# Adafruit_ESP8266_Feather_rev_E.net
KiCad netlist of a schematic drawn in EAGLE
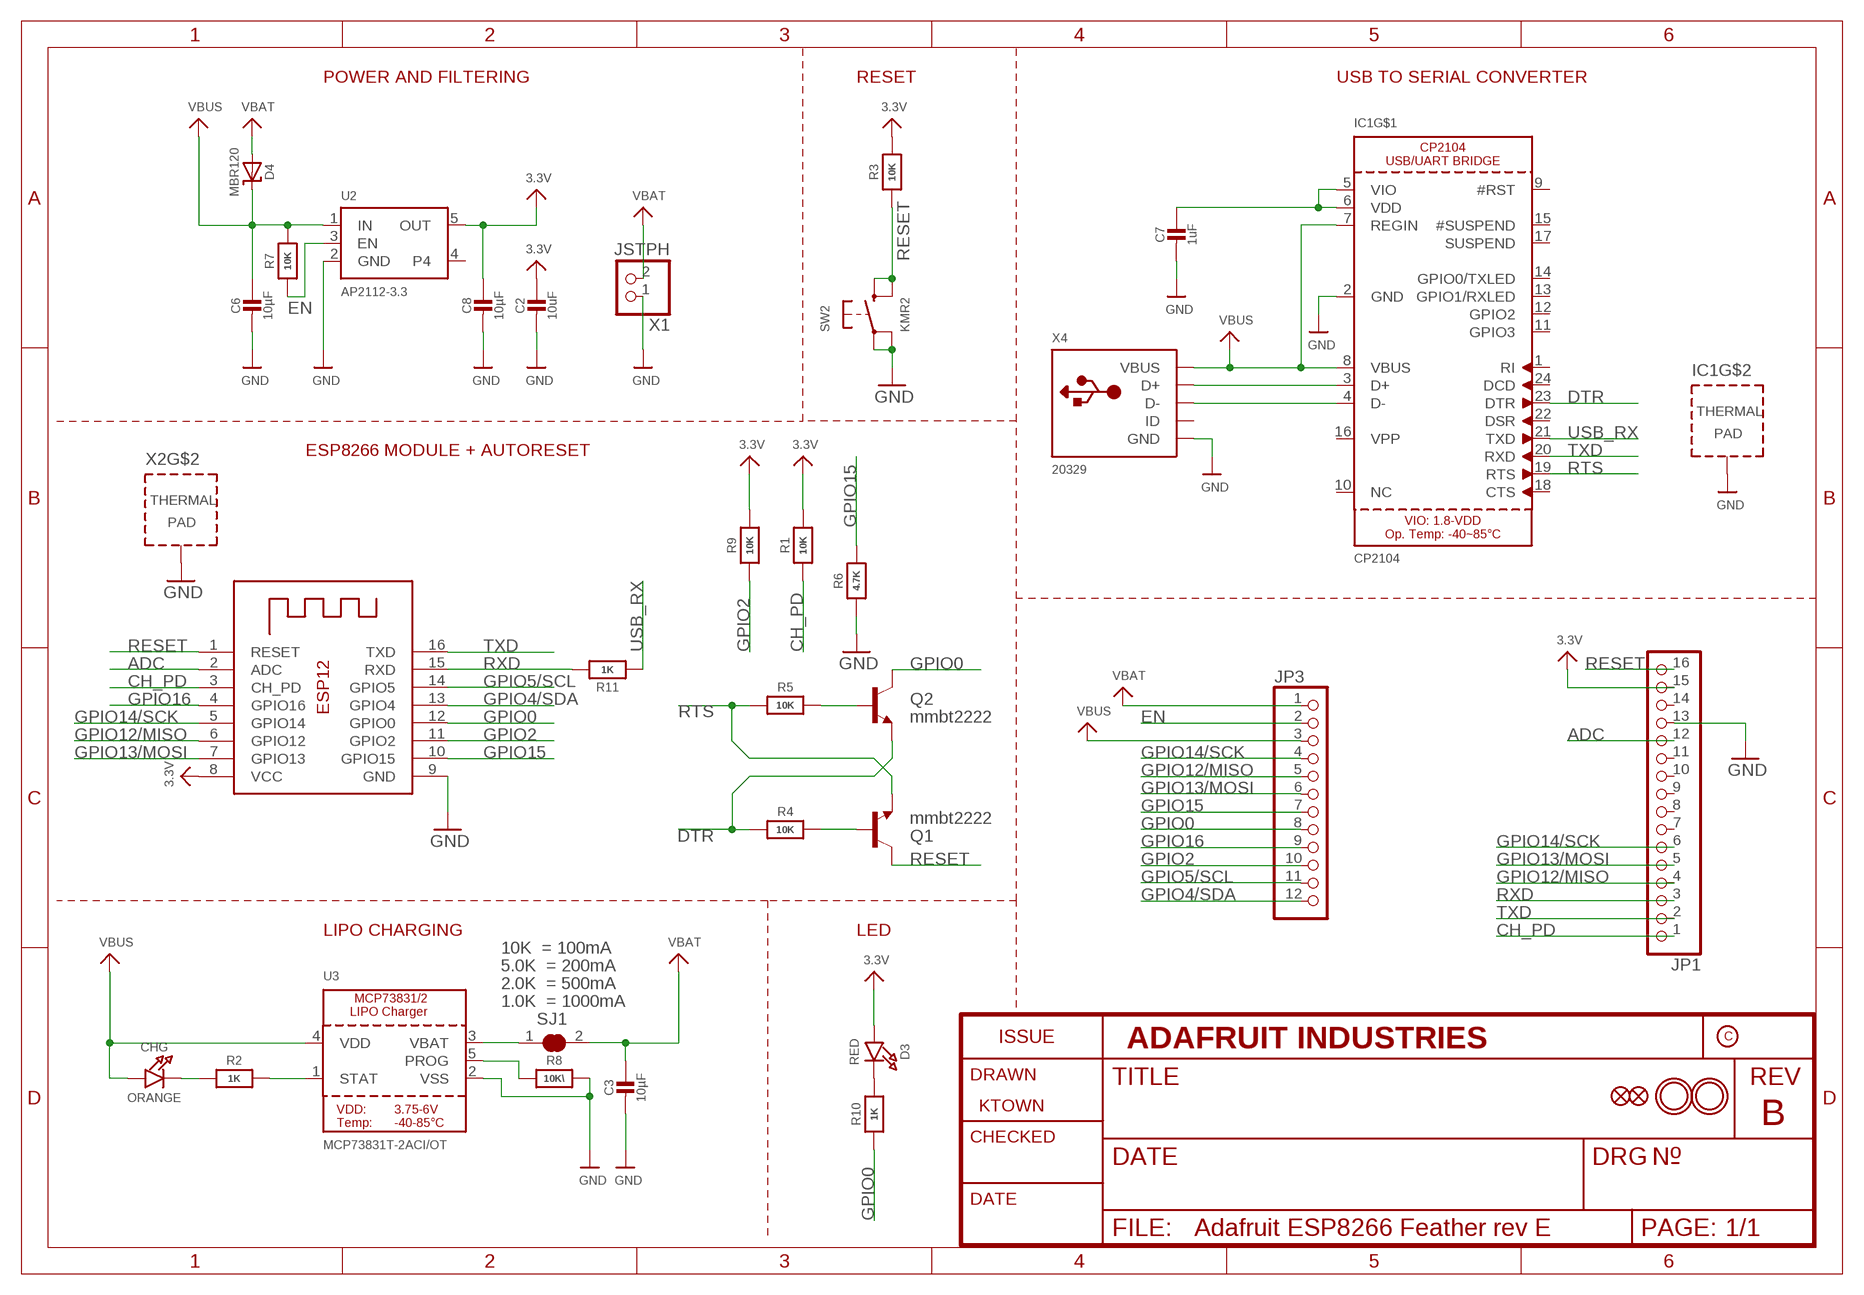
[diagram p0: schematic, sheet 1]

(export (version "E")
  (design (tool "Eeschema 10.0.6"))
  (components
    (comp (ref "C2")
      (value "10uF")
      (footprint "eagle-import:0805-NO")
      (libsource (lib "eagle-import") (part "CAP_CERAMIC0805-NOOUTLINE"))
    )
    (comp (ref "C3")
      (value "10µF")
      (footprint "eagle-import:0805-NO")
      (libsource (lib "eagle-import") (part "CAP_CERAMIC0805-NOOUTLINE"))
    )
    (comp (ref "C6")
      (value "10µF")
      (footprint "eagle-import:0805-NO")
      (libsource (lib "eagle-import") (part "CAP_CERAMIC0805-NOOUTLINE"))
    )
    (comp (ref "C7")
      (value "1uF")
      (footprint "eagle-import:0603-NO")
      (libsource (lib "eagle-import") (part "CAP_CERAMIC0603_NO"))
    )
    (comp (ref "C8")
      (value "10µF")
      (footprint "eagle-import:0805-NO")
      (libsource (lib "eagle-import") (part "CAP_CERAMIC0805-NOOUTLINE"))
    )
    (comp (ref "CHG")
      (value "ORANGE")
      (footprint "eagle-import:CHIPLED_0805_NOOUTLINE")
      (libsource (lib "eagle-import") (part "LED0805_NOOUTLINE"))
    )
    (comp (ref "D3")
      (value "RED")
      (footprint "eagle-import:CHIPLED_0805_NOOUTLINE")
      (libsource (lib "eagle-import") (part "LED0805_NOOUTLINE"))
    )
    (comp (ref "D4")
      (value "MBR120")
      (footprint "eagle-import:SOD-123")
      (libsource (lib "eagle-import") (part "DIODE-SCHOTTKYSOD-123"))
    )
    (comp (ref "IC1")
      (value "CP2104")
      (footprint "eagle-import:QFN24_4MM_SMSC")
      (libsource (lib "eagle-import") (part "CP2104"))
    )
    (comp (ref "JP1")
      (value "HEADER-1X16ROUND")
      (footprint "eagle-import:1X16_ROUND")
      (libsource (lib "eagle-import") (part "HEADER-1X16ROUND"))
    )
    (comp (ref "JP3")
      (value "HEADER-1X12")
      (footprint "eagle-import:1X12_ROUND")
      (libsource (lib "eagle-import") (part "HEADER-1X12"))
    )
    (comp (ref "Q1")
      (value "mmbt2222")
      (footprint "eagle-import:SOT23-3")
      (libsource (lib "eagle-import") (part "TRANSISTOR_NPNSOT23-3"))
    )
    (comp (ref "Q2")
      (value "mmbt2222")
      (footprint "eagle-import:SOT23-3")
      (libsource (lib "eagle-import") (part "TRANSISTOR_NPNSOT23-3"))
    )
    (comp (ref "R1")
      (value "10K")
      (footprint "eagle-import:0603-NO")
      (libsource (lib "eagle-import") (part "RESISTOR_0603_NOOUT"))
    )
    (comp (ref "R2")
      (value "1K")
      (footprint "eagle-import:0603-NO")
      (libsource (lib "eagle-import") (part "RESISTOR_0603_NOOUT"))
    )
    (comp (ref "R3")
      (value "10K")
      (footprint "eagle-import:0603-NO")
      (libsource (lib "eagle-import") (part "RESISTOR_0603_NOOUT"))
    )
    (comp (ref "R4")
      (value "10K")
      (footprint "eagle-import:0603-NO")
      (libsource (lib "eagle-import") (part "RESISTOR_0603_NOOUT"))
    )
    (comp (ref "R5")
      (value "10K")
      (footprint "eagle-import:0603-NO")
      (libsource (lib "eagle-import") (part "RESISTOR_0603_NOOUT"))
    )
    (comp (ref "R6")
      (value "4.7K")
      (footprint "eagle-import:0603-NO")
      (libsource (lib "eagle-import") (part "RESISTOR_0603_NOOUT"))
    )
    (comp (ref "R7")
      (value "10K")
      (footprint "eagle-import:0603-NO")
      (libsource (lib "eagle-import") (part "RESISTOR_0603_NOOUT"))
    )
    (comp (ref "R8")
      (value "10K\\")
      (footprint "eagle-import:0603-NO")
      (libsource (lib "eagle-import") (part "RESISTOR_0603_NOOUT"))
    )
    (comp (ref "R9")
      (value "10K")
      (footprint "eagle-import:0603-NO")
      (libsource (lib "eagle-import") (part "RESISTOR_0603_NOOUT"))
    )
    (comp (ref "R10")
      (value "1K")
      (footprint "eagle-import:0603-NO")
      (libsource (lib "eagle-import") (part "RESISTOR_0603_NOOUT"))
    )
    (comp (ref "R11")
      (value "1K")
      (footprint "eagle-import:_0603MP")
      (libsource (lib "eagle-import") (part "RESISTOR_0603MP"))
    )
    (comp (ref "SJ1")
      (value "SOLDERJUMPER_CLOSED")
      (footprint "eagle-import:SOLDERJUMPER_CLOSEDWIRE")
      (libsource (lib "eagle-import") (part "SOLDERJUMPER_CLOSED"))
    )
    (comp (ref "SW2")
      (value "KMR2")
      (footprint "eagle-import:BTN_KMR2_4.6X2.8")
      (libsource (lib "eagle-import") (part "SWITCH_TACT_SMT4.6X2.8"))
    )
    (comp (ref "U$31")
      (value "MOUNTINGHOLE2.5")
      (footprint "eagle-import:MOUNTINGHOLE_2.5_PLATED")
      (libsource (lib "eagle-import") (part "MOUNTINGHOLE2.5"))
    )
    (comp (ref "U$32")
      (value "MOUNTINGHOLE2.5")
      (footprint "eagle-import:MOUNTINGHOLE_2.5_PLATED")
      (libsource (lib "eagle-import") (part "MOUNTINGHOLE2.5"))
    )
    (comp (ref "U$34")
      (value "FIDUCIAL_1MM")
      (footprint "eagle-import:FIDUCIAL_1MM")
      (libsource (lib "eagle-import") (part "FIDUCIAL_1MM"))
    )
    (comp (ref "U$35")
      (value "FIDUCIAL_1MM")
      (footprint "eagle-import:FIDUCIAL_1MM")
      (libsource (lib "eagle-import") (part "FIDUCIAL_1MM"))
    )
    (comp (ref "U2")
      (value "AP2112-3.3")
      (footprint "eagle-import:SOT23-5")
      (libsource (lib "eagle-import") (part "VREG_SOT23-5"))
    )
    (comp (ref "U3")
      (value "MCP73831T-2ACI/OT")
      (footprint "eagle-import:SOT23-5")
      (libsource (lib "eagle-import") (part "MCP73831/2"))
    )
    (comp (ref "X1")
      (value "JSTPH")
      (footprint "eagle-import:JSTPH2")
      (libsource (lib "eagle-import") (part "CON_JST_PH_2PIN"))
    )
    (comp (ref "X2")
      (value "ESP-12")
      (footprint "eagle-import:ESP-12S")
      (libsource (lib "eagle-import") (part "ESP-12S"))
    )
    (comp (ref "X4")
      (value "20329")
      (footprint "eagle-import:4UCONN_20329_V2")
      (libsource (lib "eagle-import") (part "USB_MICRO_20329_V2"))
    )
  )
  (nets
    (net (code "1") (name "/ADC") (class "Default")
      (node (ref "JP1") (pin "12") (pinfunction "12_12") (pintype "passive"))
      (node (ref "X2") (pin "2") (pinfunction "ADC_2") (pintype "passive"))
    )
    (net (code "2") (name "/CH_PD") (class "Default")
      (node (ref "JP1") (pin "1") (pinfunction "1_1") (pintype "passive"))
      (node (ref "R1") (pin "1") (pinfunction "1_1") (pintype "passive"))
      (node (ref "X2") (pin "3") (pinfunction "CH_PD_3") (pintype "input"))
    )
    (net (code "3") (name "/DTR") (class "Default")
      (node (ref "IC1") (pin "23") (pinfunction "DTR_23") (pintype "output"))
      (node (ref "Q2") (pin "2") (pinfunction "E_2") (pintype "passive"))
      (node (ref "R4") (pin "1") (pinfunction "1_1") (pintype "passive"))
    )
    (net (code "4") (name "/EN") (class "Default")
      (node (ref "JP3") (pin "2") (pinfunction "2_2") (pintype "passive"))
      (node (ref "R7") (pin "1") (pinfunction "1_1") (pintype "passive"))
      (node (ref "U2") (pin "3") (pinfunction "EN_3") (pintype "input"))
    )
    (net (code "5") (name "/GPIO0") (class "Default")
      (node (ref "JP3") (pin "8") (pinfunction "8_8") (pintype "passive"))
      (node (ref "Q2") (pin "3") (pinfunction "C_3") (pintype "passive"))
      (node (ref "R10") (pin "1") (pinfunction "1_1") (pintype "passive"))
      (node (ref "X2") (pin "12") (pinfunction "GPIO0_12") (pintype "bidirectional"))
    )
    (net (code "6") (name "/GPIO2") (class "Default")
      (node (ref "JP3") (pin "10") (pinfunction "10_10") (pintype "passive"))
      (node (ref "R9") (pin "1") (pinfunction "1_1") (pintype "passive"))
      (node (ref "X2") (pin "11") (pinfunction "GPIO2_11") (pintype "bidirectional"))
    )
    (net (code "7") (name "/GPIO4{slash}SDA") (class "Default")
      (node (ref "JP3") (pin "12") (pinfunction "12_12") (pintype "passive"))
      (node (ref "X2") (pin "13") (pinfunction "GPIO4_13") (pintype "bidirectional"))
    )
    (net (code "8") (name "/GPIO5{slash}SCL") (class "Default")
      (node (ref "JP3") (pin "11") (pinfunction "11_11") (pintype "passive"))
      (node (ref "X2") (pin "14") (pinfunction "GPIO5_14") (pintype "bidirectional"))
    )
    (net (code "9") (name "/GPIO12{slash}MISO") (class "Default")
      (node (ref "JP1") (pin "4") (pinfunction "4_4") (pintype "passive"))
      (node (ref "JP3") (pin "5") (pinfunction "5_5") (pintype "passive"))
      (node (ref "X2") (pin "6") (pinfunction "GPIO12_6") (pintype "bidirectional"))
    )
    (net (code "10") (name "/GPIO13{slash}MOSI") (class "Default")
      (node (ref "JP1") (pin "5") (pinfunction "5_5") (pintype "passive"))
      (node (ref "JP3") (pin "6") (pinfunction "6_6") (pintype "passive"))
      (node (ref "X2") (pin "7") (pinfunction "GPIO13_7") (pintype "bidirectional"))
    )
    (net (code "11") (name "/GPIO14{slash}SCK") (class "Default")
      (node (ref "JP1") (pin "6") (pinfunction "6_6") (pintype "passive"))
      (node (ref "JP3") (pin "4") (pinfunction "4_4") (pintype "passive"))
      (node (ref "X2") (pin "5") (pinfunction "GPIO14_5") (pintype "bidirectional"))
    )
    (net (code "12") (name "/GPIO15") (class "Default")
      (node (ref "JP3") (pin "7") (pinfunction "7_7") (pintype "passive"))
      (node (ref "R6") (pin "2") (pinfunction "2_2") (pintype "passive"))
      (node (ref "X2") (pin "10") (pinfunction "GPIO15_10") (pintype "bidirectional"))
    )
    (net (code "13") (name "/GPIO16") (class "Default")
      (node (ref "JP3") (pin "9") (pinfunction "9_9") (pintype "passive"))
      (node (ref "X2") (pin "4") (pinfunction "GPIO16_4") (pintype "bidirectional"))
    )
    (net (code "14") (name "/RESET") (class "Default")
      (node (ref "JP1") (pin "16") (pinfunction "16_16") (pintype "passive"))
      (node (ref "Q1") (pin "3") (pinfunction "C_3") (pintype "passive"))
      (node (ref "R3") (pin "1") (pinfunction "1_1") (pintype "passive"))
      (node (ref "SW2") (pin "B") (pinfunction "S_B") (pintype "passive"))
      (node (ref "SW2") (pin "B'") (pinfunction "S1_B'") (pintype "passive"))
      (node (ref "X2") (pin "1") (pinfunction "RESET_1") (pintype "input"))
    )
    (net (code "15") (name "/RTS") (class "Default")
      (node (ref "IC1") (pin "19") (pinfunction "RTS_19") (pintype "output"))
      (node (ref "Q1") (pin "2") (pinfunction "E_2") (pintype "passive"))
      (node (ref "R5") (pin "1") (pinfunction "1_1") (pintype "passive"))
    )
    (net (code "16") (name "/RXD") (class "Default")
      (node (ref "JP1") (pin "3") (pinfunction "3_3") (pintype "passive"))
      (node (ref "R11") (pin "2") (pinfunction "2_2") (pintype "passive"))
      (node (ref "X2") (pin "15") (pinfunction "RXD_15") (pintype "input"))
    )
    (net (code "17") (name "/TXD") (class "Default")
      (node (ref "IC1") (pin "20") (pinfunction "RXD_20") (pintype "input"))
      (node (ref "JP1") (pin "2") (pinfunction "2_2") (pintype "passive"))
      (node (ref "X2") (pin "16") (pinfunction "TXD_16") (pintype "output"))
    )
    (net (code "18") (name "/USB_RX") (class "Default")
      (node (ref "IC1") (pin "21") (pinfunction "TXD_21") (pintype "output"))
      (node (ref "R11") (pin "1") (pinfunction "1_1") (pintype "passive"))
    )
    (net (code "19") (name "3.3V") (class "Default")
      (node (ref "C2") (pin "1") (pinfunction "1_1") (pintype "passive"))
      (node (ref "C8") (pin "1") (pinfunction "1_1") (pintype "passive"))
      (node (ref "D3") (pin "A") (pinfunction "A_A") (pintype "passive"))
      (node (ref "JP1") (pin "15") (pinfunction "15_15") (pintype "passive"))
      (node (ref "R1") (pin "2") (pinfunction "2_2") (pintype "passive"))
      (node (ref "R3") (pin "2") (pinfunction "2_2") (pintype "passive"))
      (node (ref "R9") (pin "2") (pinfunction "2_2") (pintype "passive"))
      (node (ref "U2") (pin "5") (pinfunction "OUT_5") (pintype "power_in"))
      (node (ref "X2") (pin "8") (pinfunction "VCC_8") (pintype "power_in"))
    )
    (net (code "20") (name "GND") (class "Default")
      (node (ref "C2") (pin "2") (pinfunction "2_2") (pintype "passive"))
      (node (ref "C3") (pin "2") (pinfunction "2_2") (pintype "passive"))
      (node (ref "C6") (pin "2") (pinfunction "2_2") (pintype "passive"))
      (node (ref "C7") (pin "2") (pinfunction "2_2") (pintype "passive"))
      (node (ref "C8") (pin "2") (pinfunction "2_2") (pintype "passive"))
      (node (ref "IC1") (pin "2") (pinfunction "GND_2") (pintype "power_in"))
      (node (ref "IC1") (pin "THERM") (pinfunction "TP_THERM") (pintype "power_in"))
      (node (ref "JP1") (pin "13") (pinfunction "13_13") (pintype "passive"))
      (node (ref "R6") (pin "1") (pinfunction "1_1") (pintype "passive"))
      (node (ref "R8") (pin "2") (pinfunction "2_2") (pintype "passive"))
      (node (ref "SW2") (pin "A") (pinfunction "P_A") (pintype "passive"))
      (node (ref "SW2") (pin "A'") (pinfunction "P1_A'") (pintype "passive"))
      (node (ref "U2") (pin "2") (pinfunction "GND_2") (pintype "power_in"))
      (node (ref "U3") (pin "2") (pinfunction "VSS_2") (pintype "power_in"))
      (node (ref "X1") (pin "1") (pinfunction "1_1") (pintype "passive"))
      (node (ref "X2") (pin "9") (pinfunction "GND_9") (pintype "power_in"))
      (node (ref "X2") (pin "P$1") (pinfunction "TP_P$1") (pintype "power_in"))
      (node (ref "X4") (pin "BASE@1") (pinfunction "GND_BASE@1") (pintype "power_in"))
      (node (ref "X4") (pin "BASE@2") (pinfunction "GND_BASE@2") (pintype "power_in"))
      (node (ref "X4") (pin "GND") (pinfunction "GND_GND") (pintype "power_in"))
      (node (ref "X4") (pin "SPRT@1") (pinfunction "GND_SPRT@1") (pintype "power_in"))
      (node (ref "X4") (pin "SPRT@2") (pinfunction "GND_SPRT@2") (pintype "power_in"))
      (node (ref "X4") (pin "SPRT@3") (pinfunction "GND_SPRT@3") (pintype "power_in"))
      (node (ref "X4") (pin "SPRT@4") (pinfunction "GND_SPRT@4") (pintype "power_in"))
    )
    (net (code "21") (name "Net-(CHG-PadC)") (class "Default")
      (node (ref "CHG") (pin "C") (pinfunction "C_C") (pintype "passive"))
      (node (ref "R2") (pin "1") (pinfunction "1_1") (pintype "passive"))
    )
    (net (code "22") (name "Net-(D3-PadC)") (class "Default")
      (node (ref "D3") (pin "C") (pinfunction "C_C") (pintype "passive"))
      (node (ref "R10") (pin "2") (pinfunction "2_2") (pintype "passive"))
    )
    (net (code "23") (name "Net-(IC1A-D+)") (class "Default")
      (node (ref "IC1") (pin "3") (pinfunction "D+_3") (pintype "bidirectional"))
      (node (ref "X4") (pin "D+") (pinfunction "D+_D+") (pintype "bidirectional"))
    )
    (net (code "24") (name "Net-(IC1A-D-)") (class "Default")
      (node (ref "IC1") (pin "4") (pinfunction "D-_4") (pintype "bidirectional"))
      (node (ref "X4") (pin "D-") (pinfunction "D-_D-") (pintype "bidirectional"))
    )
    (net (code "25") (name "Net-(IC1A-VDD)") (class "Default")
      (node (ref "C7") (pin "1") (pinfunction "1_1") (pintype "passive"))
      (node (ref "IC1") (pin "5") (pinfunction "VIO_5") (pintype "power_in"))
      (node (ref "IC1") (pin "6") (pinfunction "VDD_6") (pintype "power_in"))
    )
    (net (code "26") (name "Net-(Q1-B)") (class "Default")
      (node (ref "Q1") (pin "1") (pinfunction "B_1") (pintype "passive"))
      (node (ref "R4") (pin "2") (pinfunction "2_2") (pintype "passive"))
    )
    (net (code "27") (name "Net-(Q2-B)") (class "Default")
      (node (ref "Q2") (pin "1") (pinfunction "B_1") (pintype "passive"))
      (node (ref "R5") (pin "2") (pinfunction "2_2") (pintype "passive"))
    )
    (net (code "28") (name "Net-(U3-PROG)") (class "Default")
      (node (ref "R8") (pin "1") (pinfunction "1_1") (pintype "passive"))
      (node (ref "U3") (pin "5") (pinfunction "PROG_5") (pintype "input"))
    )
    (net (code "29") (name "Net-(U3-STAT)") (class "Default")
      (node (ref "R2") (pin "2") (pinfunction "2_2") (pintype "passive"))
      (node (ref "U3") (pin "1") (pinfunction "STAT_1") (pintype "output"))
    )
    (net (code "30") (name "Net-(U3-VBAT)") (class "Default")
      (node (ref "SJ1") (pin "1") (pinfunction "1_1") (pintype "passive"))
      (node (ref "U3") (pin "3") (pinfunction "VBAT_3") (pintype "power_in"))
    )
    (net (code "31") (name "VBAT") (class "Default")
      (node (ref "C3") (pin "1") (pinfunction "1_1") (pintype "passive"))
      (node (ref "D4") (pin "A") (pinfunction "A_A") (pintype "passive"))
      (node (ref "JP3") (pin "1") (pinfunction "1_1") (pintype "passive"))
      (node (ref "SJ1") (pin "2") (pinfunction "2_2") (pintype "passive"))
      (node (ref "X1") (pin "2") (pinfunction "2_2") (pintype "passive"))
    )
    (net (code "32") (name "VBUS") (class "Default")
      (node (ref "C6") (pin "1") (pinfunction "1_1") (pintype "passive"))
      (node (ref "CHG") (pin "A") (pinfunction "A_A") (pintype "passive"))
      (node (ref "D4") (pin "C") (pinfunction "C_C") (pintype "passive"))
      (node (ref "IC1") (pin "7") (pinfunction "REGIN_7") (pintype "power_in"))
      (node (ref "IC1") (pin "8") (pinfunction "VBUS_8") (pintype "power_in"))
      (node (ref "JP3") (pin "3") (pinfunction "3_3") (pintype "passive"))
      (node (ref "R7") (pin "2") (pinfunction "2_2") (pintype "passive"))
      (node (ref "U2") (pin "1") (pinfunction "IN_1") (pintype "power_in"))
      (node (ref "U3") (pin "4") (pinfunction "VDD_4") (pintype "power_in"))
      (node (ref "X4") (pin "VBUS") (pinfunction "VBUS_VBUS") (pintype "power_in"))
    )
    (net (code "33") (name "unconnected-(IC1A-#RST-Pad9)") (class "Default")
      (node (ref "IC1") (pin "9") (pinfunction "#RST_9") (pintype "bidirectional"))
    )
    (net (code "34") (name "unconnected-(IC1A-#SUSPEND-Pad15)") (class "Default")
      (node (ref "IC1") (pin "15") (pinfunction "#SUSPEND_15") (pintype "output"))
    )
    (net (code "35") (name "unconnected-(IC1A-CTS-Pad18)") (class "Default")
      (node (ref "IC1") (pin "18") (pinfunction "CTS_18") (pintype "input"))
    )
    (net (code "36") (name "unconnected-(IC1A-DCD-Pad24)") (class "Default")
      (node (ref "IC1") (pin "24") (pinfunction "DCD_24") (pintype "input"))
    )
    (net (code "37") (name "unconnected-(IC1A-DSR-Pad22)") (class "Default")
      (node (ref "IC1") (pin "22") (pinfunction "DSR_22") (pintype "input"))
    )
    (net (code "38") (name "unconnected-(IC1A-GPIO0{slash}TXLED-Pad14)") (class "Default")
      (node (ref "IC1") (pin "14") (pinfunction "GPIO0/TXLED_14") (pintype "bidirectional"))
    )
    (net (code "39") (name "unconnected-(IC1A-GPIO1{slash}RXLED-Pad13)") (class "Default")
      (node (ref "IC1") (pin "13") (pinfunction "GPIO1/RXLED_13") (pintype "bidirectional"))
    )
    (net (code "40") (name "unconnected-(IC1A-GPIO2-Pad12)") (class "Default")
      (node (ref "IC1") (pin "12") (pinfunction "GPIO2_12") (pintype "bidirectional"))
    )
    (net (code "41") (name "unconnected-(IC1A-GPIO3-Pad11)") (class "Default")
      (node (ref "IC1") (pin "11") (pinfunction "GPIO3_11") (pintype "bidirectional"))
    )
    (net (code "42") (name "unconnected-(IC1A-NC-Pad10)") (class "Default")
      (node (ref "IC1") (pin "10") (pinfunction "NC_10") (pintype "no_connect"))
    )
    (net (code "43") (name "unconnected-(IC1A-RI-Pad1)") (class "Default")
      (node (ref "IC1") (pin "1") (pinfunction "RI_1") (pintype "input"))
    )
    (net (code "44") (name "unconnected-(IC1A-SUSPEND-Pad17)") (class "Default")
      (node (ref "IC1") (pin "17") (pinfunction "SUSPEND_17") (pintype "output"))
    )
    (net (code "45") (name "unconnected-(IC1A-VPP-Pad16)") (class "Default")
      (node (ref "IC1") (pin "16") (pinfunction "VPP_16") (pintype "bidirectional"))
    )
    (net (code "46") (name "unconnected-(JP1-Pad7)") (class "Default")
      (node (ref "JP1") (pin "7") (pinfunction "7_7") (pintype "passive"))
    )
    (net (code "47") (name "unconnected-(JP1-Pad8)") (class "Default")
      (node (ref "JP1") (pin "8") (pinfunction "8_8") (pintype "passive"))
    )
    (net (code "48") (name "unconnected-(JP1-Pad9)") (class "Default")
      (node (ref "JP1") (pin "9") (pinfunction "9_9") (pintype "passive"))
    )
    (net (code "49") (name "unconnected-(JP1-Pad10)") (class "Default")
      (node (ref "JP1") (pin "10") (pinfunction "10_10") (pintype "passive"))
    )
    (net (code "50") (name "unconnected-(JP1-Pad11)") (class "Default")
      (node (ref "JP1") (pin "11") (pinfunction "11_11") (pintype "passive"))
    )
    (net (code "51") (name "unconnected-(JP1-Pad14)") (class "Default")
      (node (ref "JP1") (pin "14") (pinfunction "14_14") (pintype "passive"))
    )
    (net (code "52") (name "unconnected-(U2-P4-Pad4)") (class "Default")
      (node (ref "U2") (pin "4") (pinfunction "P4_4") (pintype "bidirectional"))
    )
    (net (code "53") (name "unconnected-(X4-PadID)") (class "Default")
      (node (ref "X4") (pin "ID") (pinfunction "ID_ID") (pintype "bidirectional"))
    )
  )
)
